# AFE.net
KiCad netlist of a schematic drawn in Altium Designer
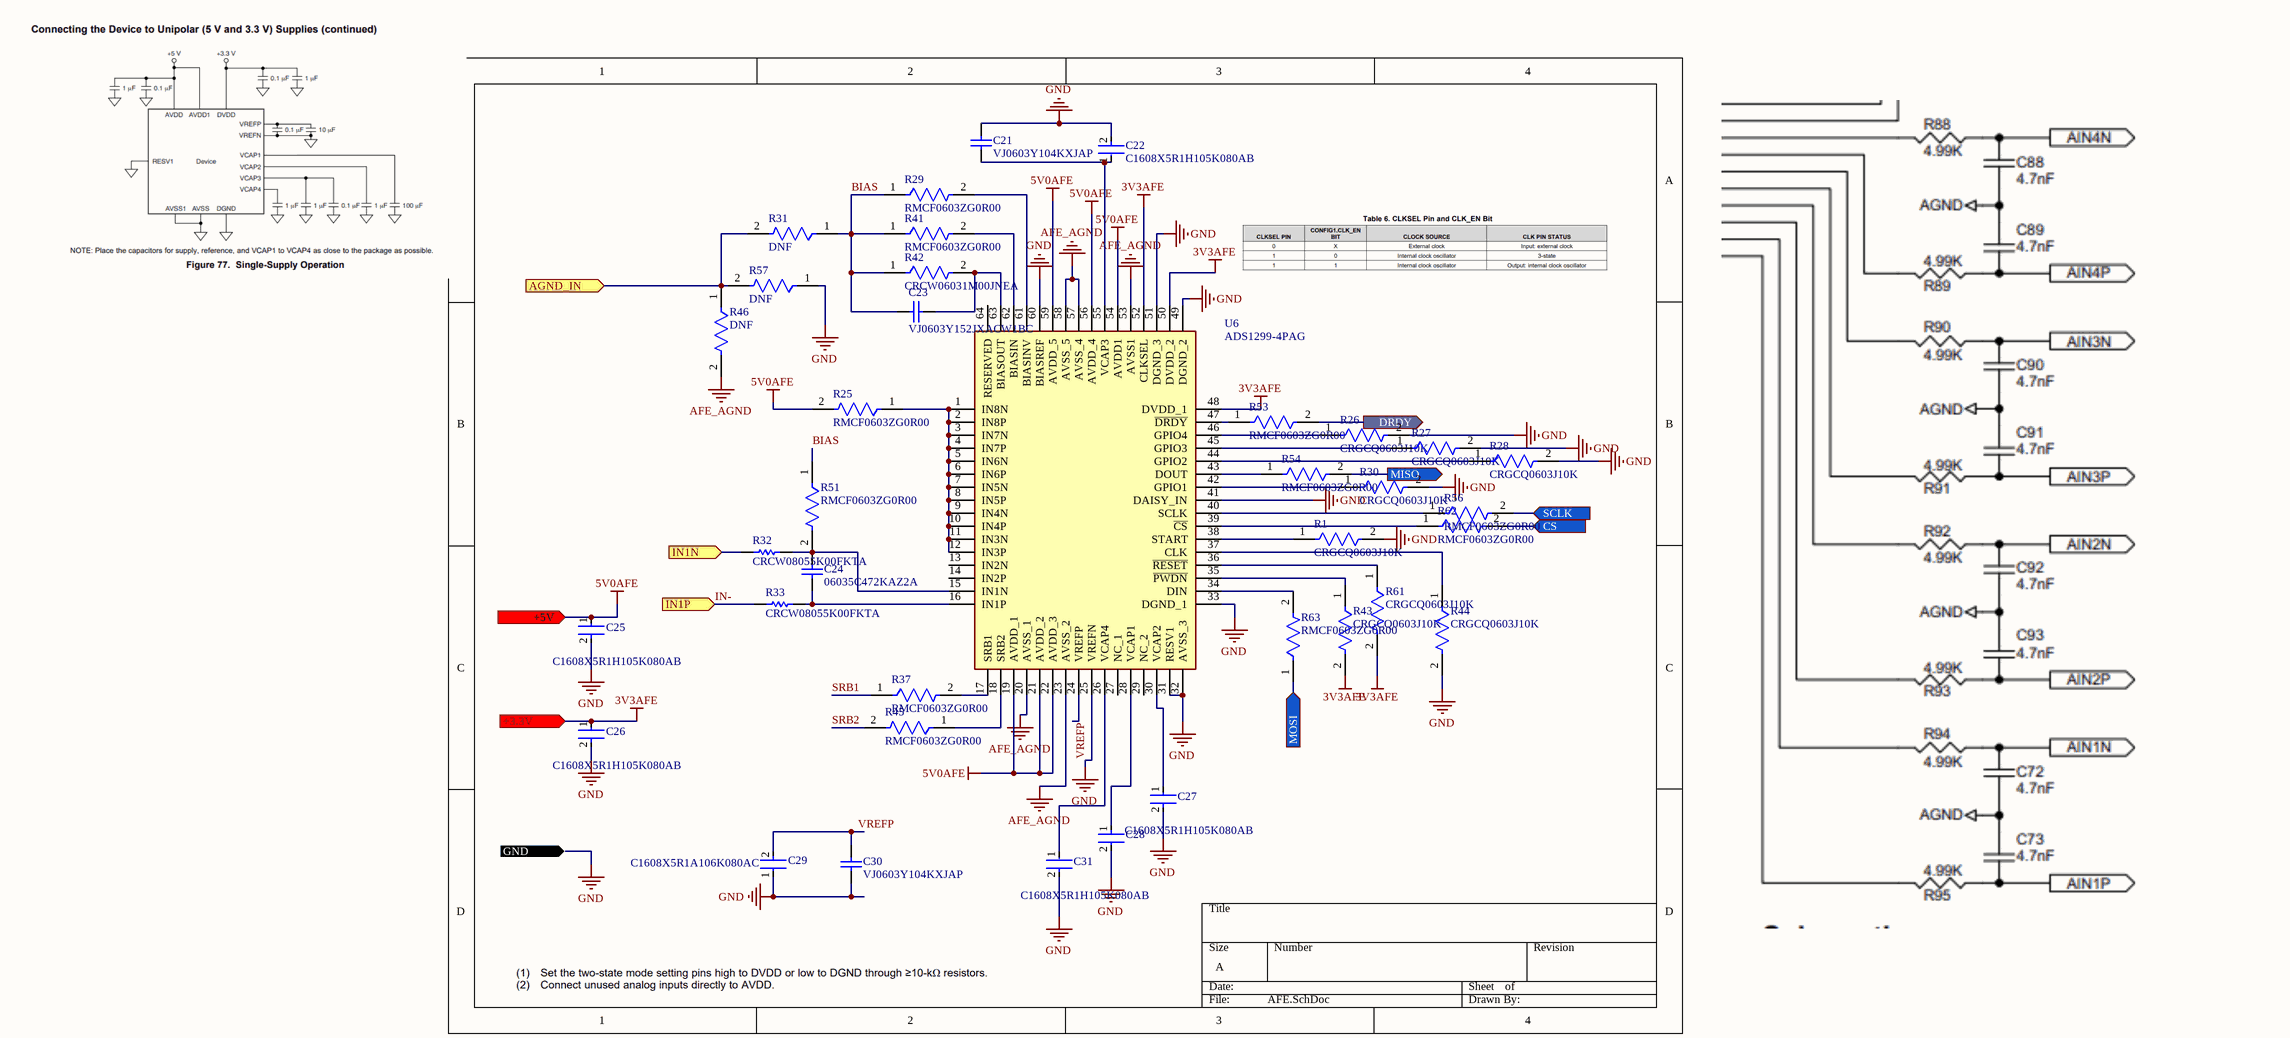
[diagram p0: AFE.SchDoc]

(export (version "E")
  (design (tool "Eeschema 10.0.6"))
  (components
    (comp (ref "C21")
      (value "VJ0603Y104KXJAP")
      (footprint "CAPC1608X92X38NL15T08")
      (fields (field (name "MANUFACTURER") "Vitramon"))
      (libsource (lib "Altium Content Vault") (part "CAP"))
    )
    (comp (ref "C22")
      (value "C1608X5R1H105K080AB")
      (footprint "FP-C1608-080-0_1-IPC_B")
      (description "Multilayer Ceramic Capacitors 1μF ±10% 50V X5R SMD 0603")
      (fields (field (name "VOLTAGE") "50V") (field (name "TOLERANCE") "10%"))
      (libsource (lib "Altium Content Vault") (part "236180d848d6139a670b325ea6854c9"))
    )
    (comp (ref "C23")
      (value "VJ0603Y152JXACW1BC")
      (footprint "CAPC1608X95X40NL15T15")
      (fields (field (name "MANUFACTURER") "Vitramon"))
      (libsource (lib "Altium Content Vault") (part "CAP"))
    )
    (comp (ref "C24")
      (value "06035C472KAZ2A")
      (footprint "CAPC1608X90X35LL15T15")
      (fields (field (name "MANUFACTURER") "AVX Interconnect / Elco"))
      (libsource (lib "Altium Content Vault") (part "CAP"))
    )
    (comp (ref "C25")
      (value "C1608X5R1H105K080AB")
      (footprint "FP-C1608-080-0_1-IPC_B")
      (description "Multilayer Ceramic Capacitors 1μF ±10% 50V X5R SMD 0603")
      (fields (field (name "VOLTAGE") "50V") (field (name "TOLERANCE") "10%"))
      (libsource (lib "Altium Content Vault") (part "236180d848d6139a670b325ea6854c9"))
    )
    (comp (ref "C26")
      (value "C1608X5R1H105K080AB")
      (footprint "FP-C1608-080-0_1-IPC_B")
      (description "Multilayer Ceramic Capacitors 1μF ±10% 50V X5R SMD 0603")
      (fields (field (name "VOLTAGE") "50V") (field (name "TOLERANCE") "10%"))
      (libsource (lib "Altium Content Vault") (part "236180d848d6139a670b325ea6854c9"))
    )
    (comp (ref "C27")
      (value "C1608X5R1H105K080AB")
      (footprint "FP-C1608-080-0_1-IPC_B")
      (description "Multilayer Ceramic Capacitors 1μF ±10% 50V X5R SMD 0603")
      (fields (field (name "VOLTAGE") "50V") (field (name "TOLERANCE") "10%"))
      (libsource (lib "Altium Content Vault") (part "236180d848d6139a670b325ea6854c9"))
    )
    (comp (ref "C28")
      (value "GRM21BR60J107ME15K")
      (footprint "FP-GRM21B-0_2-e0_2_0_7-IPC_B")
      (description "Chip Multilayer Ceramic Capacitors for General Purpose, 0805, 100uF, X5R, 15%, 20%, 6.3V")
      (fields (field (name "TOLERANCE") "20%"))
      (libsource (lib "Altium Content Vault") (part "b4654b650e69147ec39a6b967a45e02"))
    )
    (comp (ref "C29")
      (value "C1608X5R1A106K080AC")
      (footprint "FP-C1608-080-0_1-MFG")
      (description "Multilayer Ceramic Capacitors 10μF ±10% 10V X5R SMD 0603")
      (fields (field (name "VOLTAGE") "10V") (field (name "TOLERANCE") "10%"))
      (libsource (lib "Altium Content Vault") (part "236180d848d6139a670b325ea6854c9"))
    )
    (comp (ref "C30")
      (value "VJ0603Y104KXJAP")
      (footprint "CAPC1608X92X38NL15T08")
      (fields (field (name "MANUFACTURER") "Vitramon"))
      (libsource (lib "Altium Content Vault") (part "CAP"))
    )
    (comp (ref "C31")
      (value "C1608X5R1H105K080AB")
      (footprint "FP-C1608-080-0_1-IPC_B")
      (description "Multilayer Ceramic Capacitors 1μF ±10% 50V X5R SMD 0603")
      (fields (field (name "VOLTAGE") "50V") (field (name "TOLERANCE") "10%"))
      (libsource (lib "Altium Content Vault") (part "236180d848d6139a670b325ea6854c9"))
    )
    (comp (ref "R1")
      (value "CRGCQ0603J10K")
      (footprint "FP-CRGCQ0603-IPC_C")
      (description "CRGCQ 0603 10K 5%")
      (fields
        (field (name "TOLERANCE") "0.05")
        (field (name "OCTOPART") "https://octopart.com/crgcq0603j10k-te+connectivity-91018097")
      )
      (libsource (lib "Altium Content Vault") (part "1029c3af85768c4190bb7ad29bc67b5"))
    )
    (comp (ref "R25")
      (value "RMCF0603ZG0R00")
      (footprint "FP-RMCF0603-IPC_B")
      (description "0Ω ±0 0.1W 0603 Thick Film Chip Resistor AEC-Q200 compliant")
      (libsource (lib "Altium Content Vault") (part "1029c3af85768c4190bb7ad29bc67b5"))
    )
    (comp (ref "R26")
      (value "CRGCQ0603J10K")
      (footprint "FP-CRGCQ0603-IPC_C")
      (description "CRGCQ 0603 10K 5%")
      (fields
        (field (name "TOLERANCE") "0.05")
        (field (name "OCTOPART") "https://octopart.com/crgcq0603j10k-te+connectivity-91018097")
      )
      (libsource (lib "Altium Content Vault") (part "1029c3af85768c4190bb7ad29bc67b5"))
    )
    (comp (ref "R27")
      (value "CRGCQ0603J10K")
      (footprint "FP-CRGCQ0603-IPC_C")
      (description "CRGCQ 0603 10K 5%")
      (fields
        (field (name "TOLERANCE") "0.05")
        (field (name "OCTOPART") "https://octopart.com/crgcq0603j10k-te+connectivity-91018097")
      )
      (libsource (lib "Altium Content Vault") (part "1029c3af85768c4190bb7ad29bc67b5"))
    )
    (comp (ref "R28")
      (value "CRGCQ0603J10K")
      (footprint "FP-CRGCQ0603-IPC_C")
      (description "CRGCQ 0603 10K 5%")
      (fields
        (field (name "TOLERANCE") "0.05")
        (field (name "OCTOPART") "https://octopart.com/crgcq0603j10k-te+connectivity-91018097")
      )
      (libsource (lib "Altium Content Vault") (part "1029c3af85768c4190bb7ad29bc67b5"))
    )
    (comp (ref "R29")
      (value "RMCF0603ZG0R00")
      (footprint "FP-RMCF0603-IPC_B")
      (description "0Ω ±0 0.1W 0603 Thick Film Chip Resistor AEC-Q200 compliant")
      (libsource (lib "Altium Content Vault") (part "1029c3af85768c4190bb7ad29bc67b5"))
    )
    (comp (ref "R30")
      (value "CRGCQ0603J10K")
      (footprint "FP-CRGCQ0603-IPC_C")
      (description "CRGCQ 0603 10K 5%")
      (fields
        (field (name "TOLERANCE") "0.05")
        (field (name "OCTOPART") "https://octopart.com/crgcq0603j10k-te+connectivity-91018097")
      )
      (libsource (lib "Altium Content Vault") (part "1029c3af85768c4190bb7ad29bc67b5"))
    )
    (comp (ref "R31")
      (value "DNF")
      (footprint "FP-RMCF0603-IPC_B")
      (description "0Ω ±0 0.1W 0603 Thick Film Chip Resistor AEC-Q200 compliant")
      (libsource (lib "Altium Content Vault") (part "1029c3af85768c4190bb7ad29bc67b5"))
    )
    (comp (ref "R32")
      (value "CRCW08055K00FKTA")
      (footprint "RESC2013X50X30ML20T20")
      (fields (field (name "MANUFACTURER") "Vishay Dale"))
      (libsource (lib "Altium Content Vault") (part "RES"))
    )
    (comp (ref "R33")
      (value "CRCW08055K00FKTA")
      (footprint "RESC2013X50X30ML20T20")
      (fields (field (name "MANUFACTURER") "Vishay Dale"))
      (libsource (lib "Altium Content Vault") (part "RES"))
    )
    (comp (ref "R37")
      (value "RMCF0603ZG0R00")
      (footprint "FP-RMCF0603-IPC_B")
      (description "0Ω ±0 0.1W 0603 Thick Film Chip Resistor AEC-Q200 compliant")
      (libsource (lib "Altium Content Vault") (part "1029c3af85768c4190bb7ad29bc67b5"))
    )
    (comp (ref "R41")
      (value "RMCF0603ZG0R00")
      (footprint "FP-RMCF0603-IPC_B")
      (description "0Ω ±0 0.1W 0603 Thick Film Chip Resistor AEC-Q200 compliant")
      (libsource (lib "Altium Content Vault") (part "1029c3af85768c4190bb7ad29bc67b5"))
    )
    (comp (ref "R42")
      (value "CRCW06031M00JNEA")
      (footprint "FP-CRCW0603-e3-IPC_B")
      (description "RES Thick Film, 1MΩ, 5%, 0.1W, 200ppm/°C, 0603")
      (fields (field (name "TOLERANCE") "5%"))
      (libsource (lib "Altium Content Vault") (part "1029c3af85768c4190bb7ad29bc67b5"))
    )
    (comp (ref "R43")
      (value "CRGCQ0603J10K")
      (footprint "FP-CRGCQ0603-IPC_C")
      (description "CRGCQ 0603 10K 5%")
      (fields
        (field (name "TOLERANCE") "0.05")
        (field (name "OCTOPART") "https://octopart.com/crgcq0603j10k-te+connectivity-91018097")
      )
      (libsource (lib "Altium Content Vault") (part "1029c3af85768c4190bb7ad29bc67b5"))
    )
    (comp (ref "R44")
      (value "CRGCQ0603J10K")
      (footprint "FP-CRGCQ0603-IPC_C")
      (description "CRGCQ 0603 10K 5%")
      (fields
        (field (name "TOLERANCE") "0.05")
        (field (name "OCTOPART") "https://octopart.com/crgcq0603j10k-te+connectivity-91018097")
      )
      (libsource (lib "Altium Content Vault") (part "1029c3af85768c4190bb7ad29bc67b5"))
    )
    (comp (ref "R45")
      (value "RMCF0603ZG0R00")
      (footprint "FP-RMCF0603-IPC_B")
      (description "0Ω ±0 0.1W 0603 Thick Film Chip Resistor AEC-Q200 compliant")
      (libsource (lib "Altium Content Vault") (part "1029c3af85768c4190bb7ad29bc67b5"))
    )
    (comp (ref "R46")
      (value "DNF")
      (footprint "FP-RMCF0603-IPC_B")
      (description "0Ω ±0 0.1W 0603 Thick Film Chip Resistor AEC-Q200 compliant")
      (libsource (lib "Altium Content Vault") (part "1029c3af85768c4190bb7ad29bc67b5"))
    )
    (comp (ref "R51")
      (value "RMCF0603ZG0R00")
      (footprint "FP-RMCF0603-IPC_B")
      (description "0Ω ±0 0.1W 0603 Thick Film Chip Resistor AEC-Q200 compliant")
      (libsource (lib "Altium Content Vault") (part "1029c3af85768c4190bb7ad29bc67b5"))
    )
    (comp (ref "R53")
      (value "RMCF0603ZG0R00")
      (footprint "FP-RMCF0603-IPC_B")
      (description "0Ω ±0 0.1W 0603 Thick Film Chip Resistor AEC-Q200 compliant")
      (libsource (lib "Altium Content Vault") (part "1029c3af85768c4190bb7ad29bc67b5"))
    )
    (comp (ref "R54")
      (value "RMCF0603ZG0R00")
      (footprint "FP-RMCF0603-IPC_B")
      (description "0Ω ±0 0.1W 0603 Thick Film Chip Resistor AEC-Q200 compliant")
      (libsource (lib "Altium Content Vault") (part "1029c3af85768c4190bb7ad29bc67b5"))
    )
    (comp (ref "R56")
      (value "RMCF0603ZG0R00")
      (footprint "FP-RMCF0603-IPC_B")
      (description "0Ω ±0 0.1W 0603 Thick Film Chip Resistor AEC-Q200 compliant")
      (libsource (lib "Altium Content Vault") (part "1029c3af85768c4190bb7ad29bc67b5"))
    )
    (comp (ref "R57")
      (value "DNF")
      (footprint "FP-RMCF0603-IPC_B")
      (description "0Ω ±0 0.1W 0603 Thick Film Chip Resistor AEC-Q200 compliant")
      (libsource (lib "Altium Content Vault") (part "1029c3af85768c4190bb7ad29bc67b5"))
    )
    (comp (ref "R61")
      (value "CRGCQ0603J10K")
      (footprint "FP-CRGCQ0603-IPC_C")
      (description "CRGCQ 0603 10K 5%")
      (fields
        (field (name "TOLERANCE") "0.05")
        (field (name "OCTOPART") "https://octopart.com/crgcq0603j10k-te+connectivity-91018097")
      )
      (libsource (lib "Altium Content Vault") (part "1029c3af85768c4190bb7ad29bc67b5"))
    )
    (comp (ref "R62")
      (value "RMCF0603ZG0R00")
      (footprint "FP-RMCF0603-IPC_B")
      (description "0Ω ±0 0.1W 0603 Thick Film Chip Resistor AEC-Q200 compliant")
      (libsource (lib "Altium Content Vault") (part "1029c3af85768c4190bb7ad29bc67b5"))
    )
    (comp (ref "R63")
      (value "RMCF0603ZG0R00")
      (footprint "FP-RMCF0603-IPC_B")
      (description "0Ω ±0 0.1W 0603 Thick Film Chip Resistor AEC-Q200 compliant")
      (libsource (lib "Altium Content Vault") (part "1029c3af85768c4190bb7ad29bc67b5"))
    )
    (comp (ref "U6")
      (value "ADS1299-4PAG")
      (footprint "QFP50P1200X1200X120-64N")
      (description "Low-Noise, 4-Channel, 24-Bit Analog-to-Digital Converter for Biopotential Measurements")
      (fields (field (name "MOUSER PART NUMBER") "595-ADS1299-4PAG"))
      (libsource (lib "ADS1299-4PAG") (part "ADS1299-4PAG"))
    )
  )
  (nets
    (net (code "1") (name "/AGND_IN") (class "Default")
      (node (ref "R31") (pin "2") (pinfunction "2_2") (pintype "passive"))
      (node (ref "R46") (pin "1") (pinfunction "1_1") (pintype "passive"))
      (node (ref "R57") (pin "2") (pinfunction "2_2") (pintype "passive"))
    )
    (net (code "2") (name "/BIAS") (class "Default")
      (node (ref "C23") (pin "1") (pinfunction "1_1") (pintype "passive"))
      (node (ref "R29") (pin "1") (pinfunction "1_1") (pintype "passive"))
      (node (ref "R31") (pin "1") (pinfunction "1_1") (pintype "passive"))
      (node (ref "R41") (pin "1") (pinfunction "1_1") (pintype "passive"))
      (node (ref "R42") (pin "1") (pinfunction "1_1") (pintype "passive"))
      (node (ref "R51") (pin "1") (pinfunction "1_1") (pintype "passive"))
    )
    (net (code "3") (name "/CS") (class "Default")
      (node (ref "R62") (pin "2") (pinfunction "2_2") (pintype "passive"))
    )
    (net (code "4") (name "/DRDY") (class "Default")
      (node (ref "R53") (pin "2") (pinfunction "2_2") (pintype "passive"))
    )
    (net (code "5") (name "/IN-") (class "Default")
      (node (ref "R33") (pin "1") (pinfunction "1_1") (pintype "passive"))
    )
    (net (code "6") (name "/IN1N") (class "Default")
      (node (ref "R32") (pin "1") (pinfunction "1_1") (pintype "passive"))
    )
    (net (code "7") (name "/MISO") (class "Default")
      (node (ref "R54") (pin "2") (pinfunction "2_2") (pintype "passive"))
    )
    (net (code "8") (name "/MOSI") (class "Default")
      (node (ref "R63") (pin "1") (pinfunction "1_1") (pintype "passive"))
    )
    (net (code "9") (name "/SCLK") (class "Default")
      (node (ref "R56") (pin "2") (pinfunction "2_2") (pintype "passive"))
    )
    (net (code "10") (name "/SRB1") (class "Default")
      (node (ref "R37") (pin "1") (pinfunction "1_1") (pintype "passive"))
    )
    (net (code "11") (name "/SRB2") (class "Default")
      (node (ref "R45") (pin "2") (pinfunction "2_2") (pintype "passive"))
    )
    (net (code "12") (name "/VREFP") (class "Default")
      (node (ref "C29") (pin "2") (pinfunction "2_2") (pintype "passive"))
      (node (ref "C30") (pin "2") (pinfunction "2_2") (pintype "passive"))
      (node (ref "U6") (pin "24") (pinfunction "VREFP_24") (pintype "passive"))
    )
    (net (code "13") (name "3V3AFE") (class "Default")
      (node (ref "C26") (pin "1") (pinfunction "1_1") (pintype "passive"))
      (node (ref "R43") (pin "2") (pinfunction "2_2") (pintype "passive"))
      (node (ref "R61") (pin "2") (pinfunction "2_2") (pintype "passive"))
      (node (ref "U6") (pin "48") (pinfunction "DVDD_1_48") (pintype "passive"))
      (node (ref "U6") (pin "50") (pinfunction "DVDD_2_50") (pintype "passive"))
      (node (ref "U6") (pin "52") (pinfunction "CLKSEL_52") (pintype "passive"))
    )
    (net (code "14") (name "5V0AFE") (class "Default")
      (node (ref "C25") (pin "1") (pinfunction "1_1") (pintype "passive"))
      (node (ref "R25") (pin "2") (pinfunction "2_2") (pintype "passive"))
      (node (ref "U6") (pin "19") (pinfunction "AVDD_1_19") (pintype "passive"))
      (node (ref "U6") (pin "21") (pinfunction "AVDD_2_21") (pintype "passive"))
      (node (ref "U6") (pin "22") (pinfunction "AVDD_3_22") (pintype "passive"))
      (node (ref "U6") (pin "54") (pinfunction "AVDD1_54") (pintype "passive"))
      (node (ref "U6") (pin "56") (pinfunction "AVDD_4_56") (pintype "passive"))
      (node (ref "U6") (pin "59") (pinfunction "AVDD_5_59") (pintype "passive"))
    )
    (net (code "15") (name "AFE_AGND") (class "Default")
      (node (ref "R46") (pin "2") (pinfunction "2_2") (pintype "passive"))
      (node (ref "U6") (pin "20") (pinfunction "AVSS_1_20") (pintype "passive"))
      (node (ref "U6") (pin "23") (pinfunction "AVSS_2_23") (pintype "passive"))
      (node (ref "U6") (pin "53") (pinfunction "AVSS1_53") (pintype "passive"))
      (node (ref "U6") (pin "57") (pinfunction "AVSS_4_57") (pintype "passive"))
      (node (ref "U6") (pin "58") (pinfunction "AVSS_5_58") (pintype "passive"))
    )
    (net (code "16") (name "GND") (class "Default")
      (node (ref "C21") (pin "2") (pinfunction "2_2") (pintype "passive"))
      (node (ref "C22") (pin "2") (pinfunction "2_2") (pintype "passive"))
      (node (ref "C25") (pin "2") (pinfunction "2_2") (pintype "passive"))
      (node (ref "C26") (pin "2") (pinfunction "2_2") (pintype "passive"))
      (node (ref "C27") (pin "2") (pinfunction "2_2") (pintype "passive"))
      (node (ref "C28") (pin "2") (pinfunction "2_2") (pintype "passive"))
      (node (ref "C29") (pin "1") (pinfunction "1_1") (pintype "passive"))
      (node (ref "C30") (pin "1") (pinfunction "1_1") (pintype "passive"))
      (node (ref "C31") (pin "2") (pinfunction "2_2") (pintype "passive"))
      (node (ref "R1") (pin "2") (pinfunction "2_2") (pintype "passive"))
      (node (ref "R26") (pin "2") (pinfunction "2_2") (pintype "passive"))
      (node (ref "R27") (pin "2") (pinfunction "2_2") (pintype "passive"))
      (node (ref "R28") (pin "2") (pinfunction "2_2") (pintype "passive"))
      (node (ref "R30") (pin "2") (pinfunction "2_2") (pintype "passive"))
      (node (ref "R44") (pin "2") (pinfunction "2_2") (pintype "passive"))
      (node (ref "R57") (pin "1") (pinfunction "1_1") (pintype "passive"))
      (node (ref "U6") (pin "25") (pinfunction "VREFN_25") (pintype "passive"))
      (node (ref "U6") (pin "31") (pinfunction "RESV1_31") (pintype "passive"))
      (node (ref "U6") (pin "32") (pinfunction "AVSS_3_32") (pintype "passive"))
      (node (ref "U6") (pin "33") (pinfunction "DGND_1_33") (pintype "passive"))
      (node (ref "U6") (pin "41") (pinfunction "DAISY_IN_41") (pintype "passive"))
      (node (ref "U6") (pin "49") (pinfunction "DGND_2_49") (pintype "passive"))
      (node (ref "U6") (pin "51") (pinfunction "DGND_3_51") (pintype "passive"))
      (node (ref "U6") (pin "60") (pinfunction "BIASREF_60") (pintype "passive"))
    )
    (net (code "17") (name "Net-(U6-BIASIN)") (class "Default")
      (node (ref "R41") (pin "2") (pinfunction "2_2") (pintype "passive"))
      (node (ref "U6") (pin "62") (pinfunction "BIASIN_62") (pintype "passive"))
    )
    (net (code "18") (name "Net-(U6-BIASINV)") (class "Default")
      (node (ref "R29") (pin "2") (pinfunction "2_2") (pintype "passive"))
      (node (ref "U6") (pin "61") (pinfunction "BIASINV_61") (pintype "passive"))
    )
    (net (code "19") (name "Net-(U6-BIASOUT)") (class "Default")
      (node (ref "C23") (pin "2") (pinfunction "2_2") (pintype "passive"))
      (node (ref "R42") (pin "2") (pinfunction "2_2") (pintype "passive"))
      (node (ref "U6") (pin "63") (pinfunction "BIASOUT_63") (pintype "passive"))
    )
    (net (code "20") (name "Net-(U6-CLK)") (class "Default")
      (node (ref "R44") (pin "1") (pinfunction "1_1") (pintype "passive"))
      (node (ref "U6") (pin "37") (pinfunction "CLK_37") (pintype "passive"))
    )
    (net (code "21") (name "Net-(U6-DIN)") (class "Default")
      (node (ref "R63") (pin "2") (pinfunction "2_2") (pintype "passive"))
      (node (ref "U6") (pin "34") (pinfunction "DIN_34") (pintype "passive"))
    )
    (net (code "22") (name "Net-(U6-DOUT)") (class "Default")
      (node (ref "R54") (pin "1") (pinfunction "1_1") (pintype "passive"))
      (node (ref "U6") (pin "43") (pinfunction "DOUT_43") (pintype "passive"))
    )
    (net (code "23") (name "Net-(U6-GPIO1)") (class "Default")
      (node (ref "R30") (pin "1") (pinfunction "1_1") (pintype "passive"))
      (node (ref "U6") (pin "42") (pinfunction "GPIO1_42") (pintype "passive"))
    )
    (net (code "24") (name "Net-(U6-GPIO2)") (class "Default")
      (node (ref "R28") (pin "1") (pinfunction "1_1") (pintype "passive"))
      (node (ref "U6") (pin "44") (pinfunction "GPIO2_44") (pintype "passive"))
    )
    (net (code "25") (name "Net-(U6-GPIO3)") (class "Default")
      (node (ref "R27") (pin "1") (pinfunction "1_1") (pintype "passive"))
      (node (ref "U6") (pin "45") (pinfunction "GPIO3_45") (pintype "passive"))
    )
    (net (code "26") (name "Net-(U6-GPIO4)") (class "Default")
      (node (ref "R26") (pin "1") (pinfunction "1_1") (pintype "passive"))
      (node (ref "U6") (pin "46") (pinfunction "GPIO4_46") (pintype "passive"))
    )
    (net (code "27") (name "Net-(U6-IN1N)") (class "Default")
      (node (ref "C24") (pin "1") (pinfunction "1_1") (pintype "passive"))
      (node (ref "R32") (pin "2") (pinfunction "2_2") (pintype "passive"))
      (node (ref "R51") (pin "2") (pinfunction "2_2") (pintype "passive"))
      (node (ref "U6") (pin "15") (pinfunction "IN1N_15") (pintype "passive"))
    )
    (net (code "28") (name "Net-(U6-IN1P)") (class "Default")
      (node (ref "C24") (pin "2") (pinfunction "2_2") (pintype "passive"))
      (node (ref "R33") (pin "2") (pinfunction "2_2") (pintype "passive"))
      (node (ref "U6") (pin "16") (pinfunction "IN1P_16") (pintype "passive"))
    )
    (net (code "29") (name "Net-(U6-IN3N)") (class "Default")
      (node (ref "R25") (pin "1") (pinfunction "1_1") (pintype "passive"))
      (node (ref "U6") (pin "1") (pinfunction "IN8N_1") (pintype "passive"))
      (node (ref "U6") (pin "10") (pinfunction "IN4P_10") (pintype "passive"))
      (node (ref "U6") (pin "11") (pinfunction "IN3N_11") (pintype "passive"))
      (node (ref "U6") (pin "12") (pinfunction "IN3P_12") (pintype "passive"))
      (node (ref "U6") (pin "2") (pinfunction "IN8P_2") (pintype "passive"))
      (node (ref "U6") (pin "3") (pinfunction "IN7N_3") (pintype "passive"))
      (node (ref "U6") (pin "4") (pinfunction "IN7P_4") (pintype "passive"))
      (node (ref "U6") (pin "5") (pinfunction "IN6N_5") (pintype "passive"))
      (node (ref "U6") (pin "6") (pinfunction "IN6P_6") (pintype "passive"))
      (node (ref "U6") (pin "7") (pinfunction "IN5N_7") (pintype "passive"))
      (node (ref "U6") (pin "8") (pinfunction "IN5P_8") (pintype "passive"))
      (node (ref "U6") (pin "9") (pinfunction "IN4N_9") (pintype "passive"))
    )
    (net (code "30") (name "Net-(U6-SCLK)") (class "Default")
      (node (ref "R56") (pin "1") (pinfunction "1_1") (pintype "passive"))
      (node (ref "U6") (pin "40") (pinfunction "SCLK_40") (pintype "passive"))
    )
    (net (code "31") (name "Net-(U6-SRB1)") (class "Default")
      (node (ref "R37") (pin "2") (pinfunction "2_2") (pintype "passive"))
      (node (ref "U6") (pin "17") (pinfunction "SRB1_17") (pintype "passive"))
    )
    (net (code "32") (name "Net-(U6-SRB2)") (class "Default")
      (node (ref "R45") (pin "1") (pinfunction "1_1") (pintype "passive"))
      (node (ref "U6") (pin "18") (pinfunction "SRB2_18") (pintype "passive"))
    )
    (net (code "33") (name "Net-(U6-START)") (class "Default")
      (node (ref "R1") (pin "1") (pinfunction "1_1") (pintype "passive"))
      (node (ref "U6") (pin "38") (pinfunction "START_38") (pintype "passive"))
    )
    (net (code "34") (name "Net-(U6-VCAP1)") (class "Default")
      (node (ref "C28") (pin "1") (pinfunction "1_1") (pintype "passive"))
      (node (ref "U6") (pin "28") (pinfunction "VCAP1_28") (pintype "passive"))
    )
    (net (code "35") (name "Net-(U6-VCAP2)") (class "Default")
      (node (ref "C27") (pin "1") (pinfunction "1_1") (pintype "passive"))
      (node (ref "U6") (pin "30") (pinfunction "VCAP2_30") (pintype "passive"))
    )
    (net (code "36") (name "Net-(U6-VCAP3)") (class "Default")
      (node (ref "C21") (pin "1") (pinfunction "1_1") (pintype "passive"))
      (node (ref "C22") (pin "1") (pinfunction "1_1") (pintype "passive"))
      (node (ref "U6") (pin "55") (pinfunction "VCAP3_55") (pintype "passive"))
    )
    (net (code "37") (name "Net-(U6-VCAP4)") (class "Default")
      (node (ref "C31") (pin "1") (pinfunction "1_1") (pintype "passive"))
      (node (ref "U6") (pin "26") (pinfunction "VCAP4_26") (pintype "passive"))
    )
    (net (code "38") (name "Net-(U6-~{CS})") (class "Default")
      (node (ref "R62") (pin "1") (pinfunction "1_1") (pintype "passive"))
      (node (ref "U6") (pin "39") (pinfunction "~{CS}_39") (pintype "passive"))
    )
    (net (code "39") (name "Net-(U6-~{DRDY})") (class "Default")
      (node (ref "R53") (pin "1") (pinfunction "1_1") (pintype "passive"))
      (node (ref "U6") (pin "47") (pinfunction "~{DRDY}_47") (pintype "passive"))
    )
    (net (code "40") (name "Net-(U6-~{PWDN})") (class "Default")
      (node (ref "R43") (pin "1") (pinfunction "1_1") (pintype "passive"))
      (node (ref "U6") (pin "35") (pinfunction "~{PWDN}_35") (pintype "passive"))
    )
    (net (code "41") (name "Net-(U6-~{RESET})") (class "Default")
      (node (ref "R61") (pin "1") (pinfunction "1_1") (pintype "passive"))
      (node (ref "U6") (pin "36") (pinfunction "~{RESET}_36") (pintype "passive"))
    )
    (net (code "42") (name "unconnected-(U6-IN2N-Pad13)") (class "Default")
      (node (ref "U6") (pin "13") (pinfunction "IN2N_13") (pintype "passive"))
    )
    (net (code "43") (name "unconnected-(U6-IN2P-Pad14)") (class "Default")
      (node (ref "U6") (pin "14") (pinfunction "IN2P_14") (pintype "passive"))
    )
    (net (code "44") (name "unconnected-(U6-NC_1-Pad27)") (class "Default")
      (node (ref "U6") (pin "27") (pinfunction "NC_1_27") (pintype "passive"))
    )
    (net (code "45") (name "unconnected-(U6-NC_2-Pad29)") (class "Default")
      (node (ref "U6") (pin "29") (pinfunction "NC_2_29") (pintype "passive"))
    )
    (net (code "46") (name "unconnected-(U6-RESERVED-Pad64)") (class "Default")
      (node (ref "U6") (pin "64") (pinfunction "RESERVED_64") (pintype "passive"))
    )
  )
)
